# main.net
KiCad netlist of a schematic drawn in EAGLE
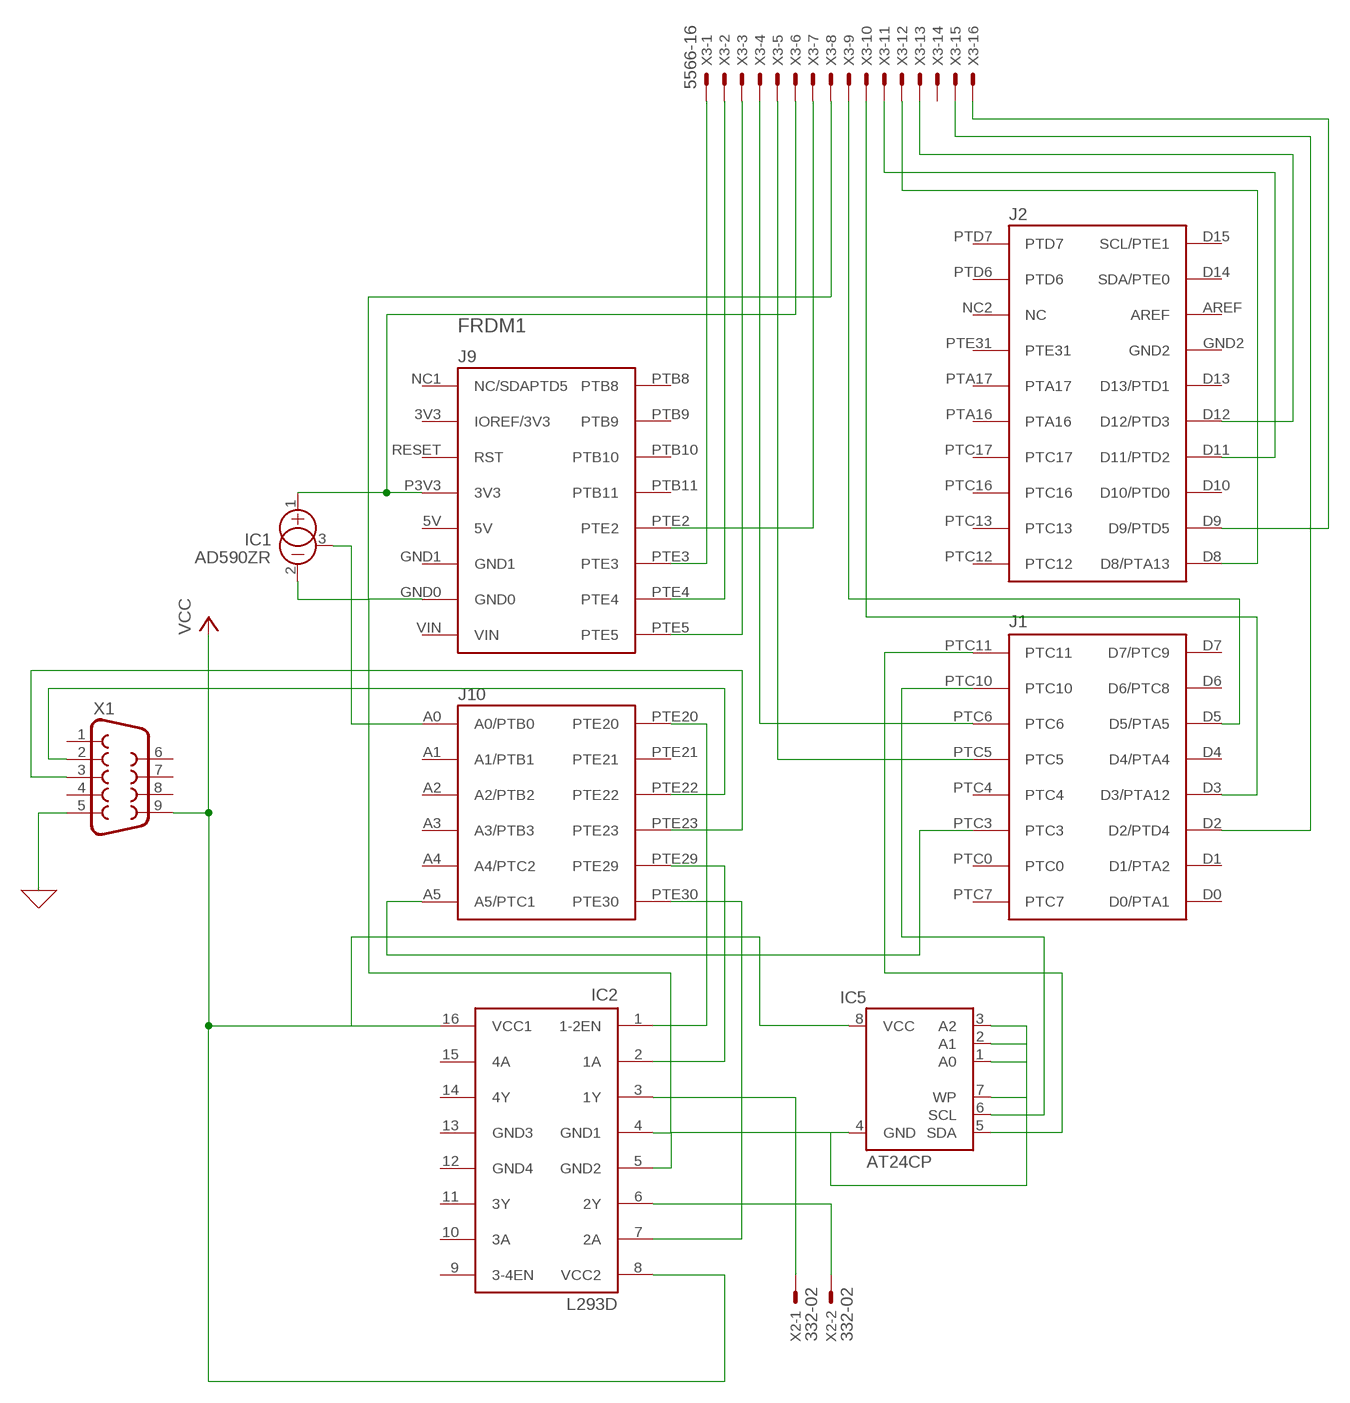
[diagram p0: schematic, sheet 1]

(export (version "E")
  (design (tool "Eeschema 10.0.6"))
  (components
    (comp (ref "FRDM1")
      (value "FRDM-KL25ZNORMAL")
      (footprint "eagle-import:FRDM_KL25Z_NORMAL")
      (libsource (lib "eagle-import") (part "FRDM-KL25ZNORMAL"))
    )
    (comp (ref "IC1")
      (value "AD590ZR")
      (footprint "eagle-import:TO92")
      (libsource (lib "eagle-import") (part "AD590ZR"))
    )
    (comp (ref "IC2")
      (value "L293D")
      (footprint "eagle-import:DIL16")
      (libsource (lib "eagle-import") (part "L293D"))
    )
    (comp (ref "IC5")
      (value "AT24CP")
      (footprint "eagle-import:DIL08")
      (fields (field (name "MPN") "AT24C1024BW-SH-B"))
      (libsource (lib "eagle-import") (part "AT24CP"))
    )
    (comp (ref "X1")
      (value "F09D")
      (footprint "eagle-import:F09D")
      (libsource (lib "eagle-import") (part "F09D"))
    )
    (comp (ref "X2")
      (value "332-02")
      (footprint "eagle-import:332-02")
      (libsource (lib "eagle-import") (part "332-02"))
    )
    (comp (ref "X3")
      (value "5566-16")
      (footprint "eagle-import:5566-16")
      (fields (field (name "MF") "MOLEX"))
      (libsource (lib "eagle-import") (part "5566-16"))
    )
  )
  (nets
    (net (code "1") (name "/GND3") (class "Default")
      (node (ref "IC2") (pin "13") (pinfunction "GND3_13") (pintype "power_in"))
    )
    (net (code "2") (name "/GND4") (class "Default")
      (node (ref "IC2") (pin "12") (pinfunction "GND4_12") (pintype "power_in"))
    )
    (net (code "3") (name "GND") (class "Default")
      (node (ref "X1") (pin "5") (pinfunction "5_5") (pintype "passive"))
    )
    (net (code "4") (name "Net-(FRDM1-3V3)") (class "Default")
      (node (ref "FRDM1") (pin "P3V3") (pinfunction "3V3_P3V3") (pintype "bidirectional"))
      (node (ref "IC1") (pin "1") (pinfunction "+_1") (pintype "input"))
      (node (ref "X3") (pin "6") (pinfunction "S_6") (pintype "passive"))
    )
    (net (code "5") (name "Net-(FRDM1-A0{slash}PTB0)") (class "Default")
      (node (ref "FRDM1") (pin "A0") (pinfunction "A0/PTB0_A0") (pintype "bidirectional"))
      (node (ref "IC1") (pin "3") (pinfunction "CAN_3") (pintype "passive"))
    )
    (net (code "6") (name "Net-(FRDM1-A5{slash}PTC1)") (class "Default")
      (node (ref "FRDM1") (pin "A5") (pinfunction "A5/PTC1_A5") (pintype "bidirectional"))
      (node (ref "FRDM1") (pin "PTC3") (pinfunction "PTC3_PTC3") (pintype "bidirectional"))
    )
    (net (code "7") (name "Net-(FRDM1-D2{slash}PTD4)") (class "Default")
      (node (ref "FRDM1") (pin "D2") (pinfunction "D2/PTD4_D2") (pintype "bidirectional"))
      (node (ref "X3") (pin "15") (pinfunction "S_15") (pintype "passive"))
    )
    (net (code "8") (name "Net-(FRDM1-D3{slash}PTA12)") (class "Default")
      (node (ref "FRDM1") (pin "D3") (pinfunction "D3/PTA12_D3") (pintype "bidirectional"))
      (node (ref "X3") (pin "10") (pinfunction "S_10") (pintype "passive"))
    )
    (net (code "9") (name "Net-(FRDM1-D5{slash}PTA5)") (class "Default")
      (node (ref "FRDM1") (pin "D5") (pinfunction "D5/PTA5_D5") (pintype "bidirectional"))
      (node (ref "X3") (pin "9") (pinfunction "S_9") (pintype "passive"))
    )
    (net (code "10") (name "Net-(FRDM1-D8{slash}PTA13)") (class "Default")
      (node (ref "FRDM1") (pin "D8") (pinfunction "D8/PTA13_D8") (pintype "bidirectional"))
      (node (ref "X3") (pin "12") (pinfunction "S_12") (pintype "passive"))
    )
    (net (code "11") (name "Net-(FRDM1-D9{slash}PTD5)") (class "Default")
      (node (ref "FRDM1") (pin "D9") (pinfunction "D9/PTD5_D9") (pintype "bidirectional"))
      (node (ref "X3") (pin "16") (pinfunction "S_16") (pintype "passive"))
    )
    (net (code "12") (name "Net-(FRDM1-D11{slash}PTD2)") (class "Default")
      (node (ref "FRDM1") (pin "D11") (pinfunction "D11/PTD2_D11") (pintype "bidirectional"))
      (node (ref "X3") (pin "11") (pinfunction "S_11") (pintype "passive"))
    )
    (net (code "13") (name "Net-(FRDM1-D12{slash}PTD3)") (class "Default")
      (node (ref "FRDM1") (pin "D12") (pinfunction "D12/PTD3_D12") (pintype "bidirectional"))
      (node (ref "X3") (pin "13") (pinfunction "S_13") (pintype "passive"))
    )
    (net (code "14") (name "Net-(FRDM1-PadPTE22)") (class "Default")
      (node (ref "FRDM1") (pin "PTE22") (pinfunction "PTE22_PTE22") (pintype "bidirectional"))
      (node (ref "X1") (pin "2") (pinfunction "2_2") (pintype "passive"))
    )
    (net (code "15") (name "Net-(FRDM1-PadPTE23)") (class "Default")
      (node (ref "FRDM1") (pin "PTE23") (pinfunction "PTE23_PTE23") (pintype "bidirectional"))
      (node (ref "X1") (pin "3") (pinfunction "3_3") (pintype "passive"))
    )
    (net (code "16") (name "Net-(IC1--)") (class "Default")
      (node (ref "FRDM1") (pin "GND0") (pinfunction "GND0_GND0") (pintype "bidirectional"))
      (node (ref "IC1") (pin "2") (pinfunction "-_2") (pintype "input"))
      (node (ref "IC2") (pin "4") (pinfunction "GND1_4") (pintype "power_in"))
      (node (ref "IC2") (pin "5") (pinfunction "GND2_5") (pintype "power_in"))
      (node (ref "IC5") (pin "1") (pinfunction "A0_1") (pintype "input"))
      (node (ref "IC5") (pin "2") (pinfunction "A1_2") (pintype "input"))
      (node (ref "IC5") (pin "3") (pinfunction "A2_3") (pintype "input"))
      (node (ref "IC5") (pin "4") (pinfunction "GND_4") (pintype "power_in"))
      (node (ref "IC5") (pin "7") (pinfunction "WP_7") (pintype "input"))
      (node (ref "X3") (pin "8") (pinfunction "S_8") (pintype "passive"))
    )
    (net (code "17") (name "Net-(IC2-1-2EN)") (class "Default")
      (node (ref "FRDM1") (pin "PTE20") (pinfunction "PTE20_PTE20") (pintype "bidirectional"))
      (node (ref "IC2") (pin "1") (pinfunction "1-2EN_1") (pintype "input"))
    )
    (net (code "18") (name "Net-(IC2-1A)") (class "Default")
      (node (ref "FRDM1") (pin "PTE29") (pinfunction "PTE29_PTE29") (pintype "bidirectional"))
      (node (ref "IC2") (pin "2") (pinfunction "1A_2") (pintype "input"))
    )
    (net (code "19") (name "Net-(IC2-1Y)") (class "Default")
      (node (ref "IC2") (pin "3") (pinfunction "1Y_3") (pintype "output"))
      (node (ref "X2") (pin "1") (pinfunction "S_1") (pintype "passive"))
    )
    (net (code "20") (name "Net-(IC2-2A)") (class "Default")
      (node (ref "FRDM1") (pin "PTE30") (pinfunction "PTE30_PTE30") (pintype "bidirectional"))
      (node (ref "IC2") (pin "7") (pinfunction "2A_7") (pintype "input"))
    )
    (net (code "21") (name "Net-(IC2-2Y)") (class "Default")
      (node (ref "IC2") (pin "6") (pinfunction "2Y_6") (pintype "output"))
      (node (ref "X2") (pin "2") (pinfunction "S_2") (pintype "passive"))
    )
    (net (code "22") (name "Net-(IC5-SCL)") (class "Default")
      (node (ref "FRDM1") (pin "PTC10") (pinfunction "PTC10_PTC10") (pintype "bidirectional"))
      (node (ref "IC5") (pin "6") (pinfunction "SCL_6") (pintype "bidirectional"))
    )
    (net (code "23") (name "Net-(IC5-SDA)") (class "Default")
      (node (ref "FRDM1") (pin "PTC11") (pinfunction "PTC11_PTC11") (pintype "bidirectional"))
      (node (ref "IC5") (pin "5") (pinfunction "SDA_5") (pintype "bidirectional"))
    )
    (net (code "24") (name "Net-(X3A-S)") (class "Default")
      (node (ref "FRDM1") (pin "PTE3") (pinfunction "PTE3_PTE3") (pintype "bidirectional"))
      (node (ref "X3") (pin "1") (pinfunction "S_1") (pintype "passive"))
    )
    (net (code "25") (name "Net-(X3I-S)") (class "Default")
      (node (ref "FRDM1") (pin "PTE4") (pinfunction "PTE4_PTE4") (pintype "bidirectional"))
      (node (ref "X3") (pin "2") (pinfunction "S_2") (pintype "passive"))
    )
    (net (code "26") (name "Net-(X3J-S)") (class "Default")
      (node (ref "FRDM1") (pin "PTE5") (pinfunction "PTE5_PTE5") (pintype "bidirectional"))
      (node (ref "X3") (pin "3") (pinfunction "S_3") (pintype "passive"))
    )
    (net (code "27") (name "Net-(X3K-S)") (class "Default")
      (node (ref "FRDM1") (pin "PTC6") (pinfunction "PTC6_PTC6") (pintype "bidirectional"))
      (node (ref "X3") (pin "4") (pinfunction "S_4") (pintype "passive"))
    )
    (net (code "28") (name "Net-(X3L-S)") (class "Default")
      (node (ref "FRDM1") (pin "PTC5") (pinfunction "PTC5_PTC5") (pintype "bidirectional"))
      (node (ref "X3") (pin "5") (pinfunction "S_5") (pintype "passive"))
    )
    (net (code "29") (name "Net-(X3N-S)") (class "Default")
      (node (ref "FRDM1") (pin "PTE2") (pinfunction "PTE2_PTE2") (pintype "bidirectional"))
      (node (ref "X3") (pin "7") (pinfunction "S_7") (pintype "passive"))
    )
    (net (code "30") (name "VCC") (class "Default")
      (node (ref "IC2") (pin "16") (pinfunction "VCC1_16") (pintype "power_in"))
      (node (ref "IC2") (pin "8") (pinfunction "VCC2_8") (pintype "power_in"))
      (node (ref "IC5") (pin "8") (pinfunction "VCC_8") (pintype "power_in"))
      (node (ref "X1") (pin "9") (pinfunction "9_9") (pintype "passive"))
    )
    (net (code "31") (name "unconnected-(FRDM1-A1{slash}PTB1-PadA1)") (class "Default")
      (node (ref "FRDM1") (pin "A1") (pinfunction "A1/PTB1_A1") (pintype "bidirectional"))
    )
    (net (code "32") (name "unconnected-(FRDM1-A2{slash}PTB2-PadA2)") (class "Default")
      (node (ref "FRDM1") (pin "A2") (pinfunction "A2/PTB2_A2") (pintype "bidirectional"))
    )
    (net (code "33") (name "unconnected-(FRDM1-A3{slash}PTB3-PadA3)") (class "Default")
      (node (ref "FRDM1") (pin "A3") (pinfunction "A3/PTB3_A3") (pintype "bidirectional"))
    )
    (net (code "34") (name "unconnected-(FRDM1-A4{slash}PTC2-PadA4)") (class "Default")
      (node (ref "FRDM1") (pin "A4") (pinfunction "A4/PTC2_A4") (pintype "bidirectional"))
    )
    (net (code "35") (name "unconnected-(FRDM1-D0{slash}PTA1-PadD0)") (class "Default")
      (node (ref "FRDM1") (pin "D0") (pinfunction "D0/PTA1_D0") (pintype "bidirectional"))
    )
    (net (code "36") (name "unconnected-(FRDM1-D1{slash}PTA2-PadD1)") (class "Default")
      (node (ref "FRDM1") (pin "D1") (pinfunction "D1/PTA2_D1") (pintype "bidirectional"))
    )
    (net (code "37") (name "unconnected-(FRDM1-D4{slash}PTA4-PadD4)") (class "Default")
      (node (ref "FRDM1") (pin "D4") (pinfunction "D4/PTA4_D4") (pintype "bidirectional"))
    )
    (net (code "38") (name "unconnected-(FRDM1-D6{slash}PTC8-PadD6)") (class "Default")
      (node (ref "FRDM1") (pin "D6") (pinfunction "D6/PTC8_D6") (pintype "bidirectional"))
    )
    (net (code "39") (name "unconnected-(FRDM1-D7{slash}PTC9-PadD7)") (class "Default")
      (node (ref "FRDM1") (pin "D7") (pinfunction "D7/PTC9_D7") (pintype "bidirectional"))
    )
    (net (code "40") (name "unconnected-(FRDM1-D10{slash}PTD0-PadD10)") (class "Default")
      (node (ref "FRDM1") (pin "D10") (pinfunction "D10/PTD0_D10") (pintype "bidirectional"))
    )
    (net (code "41") (name "unconnected-(FRDM1-D13{slash}PTD1-PadD13)") (class "Default")
      (node (ref "FRDM1") (pin "D13") (pinfunction "D13/PTD1_D13") (pintype "bidirectional"))
    )
    (net (code "42") (name "unconnected-(FRDM1-IOREF{slash}3V3-Pad3V3)") (class "Default")
      (node (ref "FRDM1") (pin "3V3") (pinfunction "IOREF/3V3_3V3") (pintype "bidirectional"))
    )
    (net (code "43") (name "unconnected-(FRDM1-NC-PadNC2)") (class "Default")
      (node (ref "FRDM1") (pin "NC2") (pinfunction "NC_NC2") (pintype "bidirectional"))
    )
    (net (code "44") (name "unconnected-(FRDM1-NC{slash}SDAPTD5-PadNC1)") (class "Default")
      (node (ref "FRDM1") (pin "NC1") (pinfunction "NC/SDAPTD5_NC1") (pintype "bidirectional"))
    )
    (net (code "45") (name "unconnected-(FRDM1-Pad5V)") (class "Default")
      (node (ref "FRDM1") (pin "5V") (pinfunction "5V_5V") (pintype "bidirectional"))
    )
    (net (code "46") (name "unconnected-(FRDM1-PadAREF)") (class "Default")
      (node (ref "FRDM1") (pin "AREF") (pinfunction "AREF_AREF") (pintype "bidirectional"))
    )
    (net (code "47") (name "unconnected-(FRDM1-PadGND1)") (class "Default")
      (node (ref "FRDM1") (pin "GND1") (pinfunction "GND1_GND1") (pintype "bidirectional"))
    )
    (net (code "48") (name "unconnected-(FRDM1-PadGND2)") (class "Default")
      (node (ref "FRDM1") (pin "GND2") (pinfunction "GND2_GND2") (pintype "bidirectional"))
    )
    (net (code "49") (name "unconnected-(FRDM1-PadPTA16)") (class "Default")
      (node (ref "FRDM1") (pin "PTA16") (pinfunction "PTA16_PTA16") (pintype "bidirectional"))
    )
    (net (code "50") (name "unconnected-(FRDM1-PadPTA17)") (class "Default")
      (node (ref "FRDM1") (pin "PTA17") (pinfunction "PTA17_PTA17") (pintype "bidirectional"))
    )
    (net (code "51") (name "unconnected-(FRDM1-PadPTB8)") (class "Default")
      (node (ref "FRDM1") (pin "PTB8") (pinfunction "PTB8_PTB8") (pintype "bidirectional"))
    )
    (net (code "52") (name "unconnected-(FRDM1-PadPTB9)") (class "Default")
      (node (ref "FRDM1") (pin "PTB9") (pinfunction "PTB9_PTB9") (pintype "bidirectional"))
    )
    (net (code "53") (name "unconnected-(FRDM1-PadPTB10)") (class "Default")
      (node (ref "FRDM1") (pin "PTB10") (pinfunction "PTB10_PTB10") (pintype "bidirectional"))
    )
    (net (code "54") (name "unconnected-(FRDM1-PadPTB11)") (class "Default")
      (node (ref "FRDM1") (pin "PTB11") (pinfunction "PTB11_PTB11") (pintype "bidirectional"))
    )
    (net (code "55") (name "unconnected-(FRDM1-PadPTC0)") (class "Default")
      (node (ref "FRDM1") (pin "PTC0") (pinfunction "PTC0_PTC0") (pintype "bidirectional"))
    )
    (net (code "56") (name "unconnected-(FRDM1-PadPTC4)") (class "Default")
      (node (ref "FRDM1") (pin "PTC4") (pinfunction "PTC4_PTC4") (pintype "bidirectional"))
    )
    (net (code "57") (name "unconnected-(FRDM1-PadPTC7)") (class "Default")
      (node (ref "FRDM1") (pin "PTC7") (pinfunction "PTC7_PTC7") (pintype "bidirectional"))
    )
    (net (code "58") (name "unconnected-(FRDM1-PadPTC12)") (class "Default")
      (node (ref "FRDM1") (pin "PTC12") (pinfunction "PTC12_PTC12") (pintype "bidirectional"))
    )
    (net (code "59") (name "unconnected-(FRDM1-PadPTC13)") (class "Default")
      (node (ref "FRDM1") (pin "PTC13") (pinfunction "PTC13_PTC13") (pintype "bidirectional"))
    )
    (net (code "60") (name "unconnected-(FRDM1-PadPTC16)") (class "Default")
      (node (ref "FRDM1") (pin "PTC16") (pinfunction "PTC16_PTC16") (pintype "bidirectional"))
    )
    (net (code "61") (name "unconnected-(FRDM1-PadPTC17)") (class "Default")
      (node (ref "FRDM1") (pin "PTC17") (pinfunction "PTC17_PTC17") (pintype "bidirectional"))
    )
    (net (code "62") (name "unconnected-(FRDM1-PadPTD6)") (class "Default")
      (node (ref "FRDM1") (pin "PTD6") (pinfunction "PTD6_PTD6") (pintype "bidirectional"))
    )
    (net (code "63") (name "unconnected-(FRDM1-PadPTD7)") (class "Default")
      (node (ref "FRDM1") (pin "PTD7") (pinfunction "PTD7_PTD7") (pintype "bidirectional"))
    )
    (net (code "64") (name "unconnected-(FRDM1-PadPTE21)") (class "Default")
      (node (ref "FRDM1") (pin "PTE21") (pinfunction "PTE21_PTE21") (pintype "bidirectional"))
    )
    (net (code "65") (name "unconnected-(FRDM1-PadPTE31)") (class "Default")
      (node (ref "FRDM1") (pin "PTE31") (pinfunction "PTE31_PTE31") (pintype "bidirectional"))
    )
    (net (code "66") (name "unconnected-(FRDM1-PadVIN)") (class "Default")
      (node (ref "FRDM1") (pin "VIN") (pinfunction "VIN_VIN") (pintype "bidirectional"))
    )
    (net (code "67") (name "unconnected-(FRDM1-RST-PadRESET)") (class "Default")
      (node (ref "FRDM1") (pin "RESET") (pinfunction "RST_RESET") (pintype "bidirectional"))
    )
    (net (code "68") (name "unconnected-(FRDM1-SCL{slash}PTE1-PadD15)") (class "Default")
      (node (ref "FRDM1") (pin "D15") (pinfunction "SCL/PTE1_D15") (pintype "bidirectional"))
    )
    (net (code "69") (name "unconnected-(FRDM1-SDA{slash}PTE0-PadD14)") (class "Default")
      (node (ref "FRDM1") (pin "D14") (pinfunction "SDA/PTE0_D14") (pintype "bidirectional"))
    )
    (net (code "70") (name "unconnected-(IC2-3-4EN-Pad9)") (class "Default")
      (node (ref "IC2") (pin "9") (pinfunction "3-4EN_9") (pintype "input"))
    )
    (net (code "71") (name "unconnected-(IC2-3A-Pad10)") (class "Default")
      (node (ref "IC2") (pin "10") (pinfunction "3A_10") (pintype "input"))
    )
    (net (code "72") (name "unconnected-(IC2-3Y-Pad11)") (class "Default")
      (node (ref "IC2") (pin "11") (pinfunction "3Y_11") (pintype "output"))
    )
    (net (code "73") (name "unconnected-(IC2-4A-Pad15)") (class "Default")
      (node (ref "IC2") (pin "15") (pinfunction "4A_15") (pintype "input"))
    )
    (net (code "74") (name "unconnected-(IC2-4Y-Pad14)") (class "Default")
      (node (ref "IC2") (pin "14") (pinfunction "4Y_14") (pintype "output"))
    )
    (net (code "75") (name "unconnected-(X1-Pad1)") (class "Default")
      (node (ref "X1") (pin "1") (pinfunction "1_1") (pintype "passive"))
    )
    (net (code "76") (name "unconnected-(X1-Pad4)") (class "Default")
      (node (ref "X1") (pin "4") (pinfunction "4_4") (pintype "passive"))
    )
    (net (code "77") (name "unconnected-(X1-Pad6)") (class "Default")
      (node (ref "X1") (pin "6") (pinfunction "6_6") (pintype "passive"))
    )
    (net (code "78") (name "unconnected-(X1-Pad7)") (class "Default")
      (node (ref "X1") (pin "7") (pinfunction "7_7") (pintype "passive"))
    )
    (net (code "79") (name "unconnected-(X1-Pad8)") (class "Default")
      (node (ref "X1") (pin "8") (pinfunction "8_8") (pintype "passive"))
    )
    (net (code "80") (name "unconnected-(X3F-S-Pad14)") (class "Default")
      (node (ref "X3") (pin "14") (pinfunction "S_14") (pintype "passive"))
    )
  )
)
